# ESC.net
KiCad netlist of a schematic drawn in Altium Designer
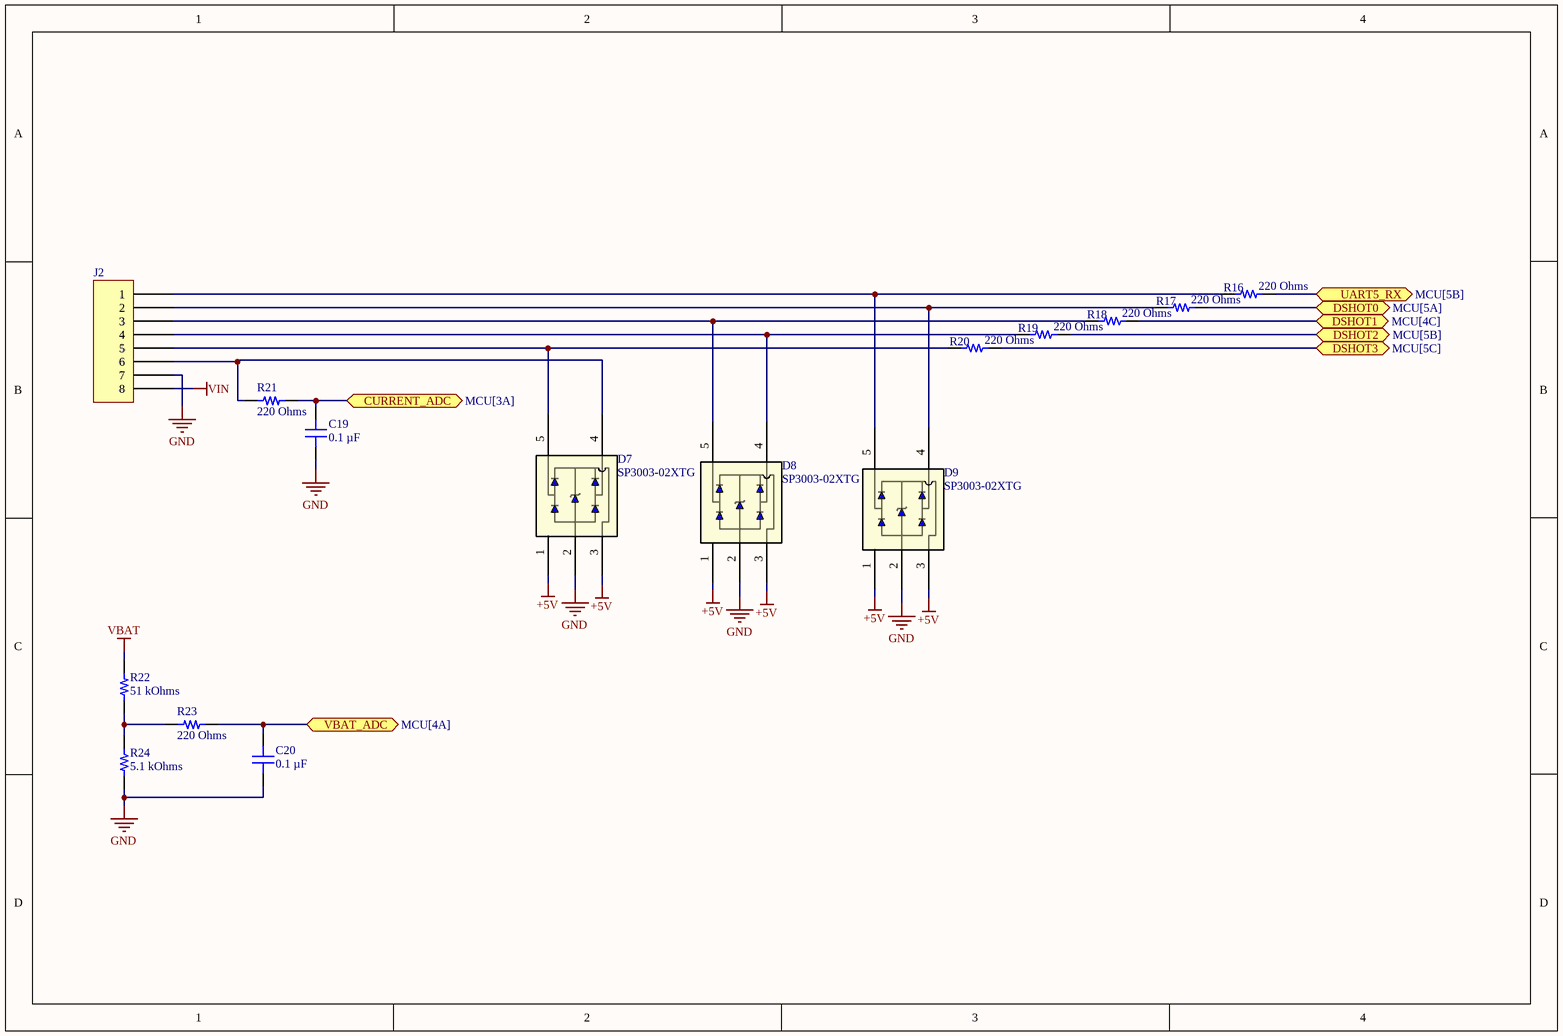
[diagram p0: ESC.SchDoc]

(export (version "E")
  (design (tool "Eeschema 10.0.6"))
  (components
    (comp (ref "C19")
      (value "0.1 µF")
      (footprint "CAP 0402_1005")
      (description "CAP CER 0.1UF 25V X7R 0402")
      (fields
        (field (name "PART NUMBER") "CGA2B3X7R1E104K050BB")
        (field (name "CAPACITANCE") "0.1 µF")
        (field (name "MANUFACTURER") "TDK Corporation")
      )
      (libsource (lib "Celestial Altium Library - altium_library") (part "Capacitor"))
    )
    (comp (ref "C20")
      (value "0.1 µF")
      (footprint "CAP 0402_1005")
      (description "CAP CER 0.1UF 25V X7R 0402")
      (fields
        (field (name "PART NUMBER") "CGA2B3X7R1E104K050BB")
        (field (name "CAPACITANCE") "0.1 µF")
        (field (name "MANUFACTURER") "TDK Corporation")
      )
      (libsource (lib "Celestial Altium Library - altium_library") (part "Capacitor"))
    )
    (comp (ref "D7")
      (value "SP3003-02XTG")
      (footprint "SP3003-02XTG")
      (description "15V Clamp 2.5A (8/20µs) Ipp Tvs Diode Surface Mount SOT-553")
      (fields (field (name "MANUFACTURER") "Littelfuse Inc."))
      (libsource (lib "PCB_Lib") (part "SP3003-02XTG"))
    )
    (comp (ref "D8")
      (value "SP3003-02XTG")
      (footprint "SP3003-02XTG")
      (description "15V Clamp 2.5A (8/20µs) Ipp Tvs Diode Surface Mount SOT-553")
      (fields (field (name "MANUFACTURER") "Littelfuse Inc."))
      (libsource (lib "PCB_Lib") (part "SP3003-02XTG"))
    )
    (comp (ref "D9")
      (value "SP3003-02XTG")
      (footprint "SP3003-02XTG")
      (description "15V Clamp 2.5A (8/20µs) Ipp Tvs Diode Surface Mount SOT-553")
      (fields (field (name "MANUFACTURER") "Littelfuse Inc."))
      (libsource (lib "PCB_Lib") (part "SP3003-02XTG"))
    )
    (comp (ref "J2")
      (value "SM08B-SRSS-TB(LF)(SN)")
      (footprint "JST SM08B-SRSS-TB")
      (description "CONN HEADER SMD R/A 8POS 1MM")
      (fields (field (name "MANUFACTURER") "JST Sales America Inc."))
      (libsource (lib "Celestial Altium Library - altium_library") (part "8 Pin"))
    )
    (comp (ref "R16")
      (value "220 Ohms")
      (footprint "YAGEO RES 0402_1005")
      (description "RES SMD 220 OHM 5% 1/16W 0402")
      (fields (field (name "PART NUMBER") "AC0402JR-07220RL") (field (name "MANUFACTURER") "Yageo"))
      (libsource (lib "Celestial Altium Library - altium_library") (part "Resistor"))
    )
    (comp (ref "R17")
      (value "220 Ohms")
      (footprint "YAGEO RES 0402_1005")
      (description "RES SMD 220 OHM 5% 1/16W 0402")
      (fields (field (name "PART NUMBER") "AC0402JR-07220RL") (field (name "MANUFACTURER") "Yageo"))
      (libsource (lib "Celestial Altium Library - altium_library") (part "Resistor"))
    )
    (comp (ref "R18")
      (value "220 Ohms")
      (footprint "YAGEO RES 0402_1005")
      (description "RES SMD 220 OHM 5% 1/16W 0402")
      (fields (field (name "PART NUMBER") "AC0402JR-07220RL") (field (name "MANUFACTURER") "Yageo"))
      (libsource (lib "Celestial Altium Library - altium_library") (part "Resistor"))
    )
    (comp (ref "R19")
      (value "220 Ohms")
      (footprint "YAGEO RES 0402_1005")
      (description "RES SMD 220 OHM 5% 1/16W 0402")
      (fields (field (name "PART NUMBER") "AC0402JR-07220RL") (field (name "MANUFACTURER") "Yageo"))
      (libsource (lib "Celestial Altium Library - altium_library") (part "Resistor"))
    )
    (comp (ref "R20")
      (value "220 Ohms")
      (footprint "YAGEO RES 0402_1005")
      (description "RES SMD 220 OHM 5% 1/16W 0402")
      (fields (field (name "PART NUMBER") "AC0402JR-07220RL") (field (name "MANUFACTURER") "Yageo"))
      (libsource (lib "Celestial Altium Library - altium_library") (part "Resistor"))
    )
    (comp (ref "R21")
      (value "220 Ohms")
      (footprint "YAGEO RES 0402_1005")
      (description "RES SMD 220 OHM 5% 1/16W 0402")
      (fields (field (name "PART NUMBER") "AC0402JR-07220RL") (field (name "MANUFACTURER") "Yageo"))
      (libsource (lib "Celestial Altium Library - altium_library") (part "Resistor"))
    )
    (comp (ref "R22")
      (value "51 kOhms")
      (footprint "RES 0603_1608")
      (description "RES SMD 51K OHM 1% 1/3W 0603")
      (fields (field (name "PART NUMBER") "CRCW060351K0FKEAHP") (field (name "MANUFACTURER") "Vishay Dale"))
      (libsource (lib "Celestial Altium Library - altium_library") (part "Resistor"))
    )
    (comp (ref "R23")
      (value "220 Ohms")
      (footprint "YAGEO RES 0402_1005")
      (description "RES SMD 220 OHM 5% 1/16W 0402")
      (fields (field (name "PART NUMBER") "AC0402JR-07220RL") (field (name "MANUFACTURER") "Yageo"))
      (libsource (lib "Celestial Altium Library - altium_library") (part "Resistor"))
    )
    (comp (ref "R24")
      (value "5.1 kOhms")
      (footprint "RES 0603_1608")
      (description "RES SMD 5.1K OHM 1% 1/3W 0603")
      (fields
        (field (name "PART NUMBER") "ERJ-PA3F5101V")
        (field (name "MANUFACTURER") "Panasonic Electronic Components")
      )
      (libsource (lib "Celestial Altium Library - altium_library") (part "Resistor"))
    )
  )
  (nets
    (net (code "1") (name "+5V") (class "Default")
      (node (ref "D7") (pin "1") (pinfunction "1_1") (pintype "passive"))
      (node (ref "D7") (pin "3") (pinfunction "3_3") (pintype "passive"))
      (node (ref "D8") (pin "1") (pinfunction "1_1") (pintype "passive"))
      (node (ref "D8") (pin "3") (pinfunction "3_3") (pintype "passive"))
      (node (ref "D9") (pin "1") (pinfunction "1_1") (pintype "passive"))
      (node (ref "D9") (pin "3") (pinfunction "3_3") (pintype "passive"))
    )
    (net (code "2") (name "/CURRENT_ADC") (class "Default")
      (node (ref "C19") (pin "1") (pinfunction "1_1") (pintype "passive"))
      (node (ref "R21") (pin "1") (pinfunction "1_1") (pintype "passive"))
    )
    (net (code "3") (name "/DSHOT0") (class "Default")
      (node (ref "R17") (pin "2") (pinfunction "2_2") (pintype "passive"))
    )
    (net (code "4") (name "/DSHOT1") (class "Default")
      (node (ref "R18") (pin "2") (pinfunction "2_2") (pintype "passive"))
    )
    (net (code "5") (name "/DSHOT2") (class "Default")
      (node (ref "R19") (pin "2") (pinfunction "2_2") (pintype "passive"))
    )
    (net (code "6") (name "/DSHOT3") (class "Default")
      (node (ref "R20") (pin "2") (pinfunction "2_2") (pintype "passive"))
    )
    (net (code "7") (name "/UART5_RX") (class "Default")
      (node (ref "R16") (pin "2") (pinfunction "2_2") (pintype "passive"))
    )
    (net (code "8") (name "/VBAT_ADC") (class "Default")
      (node (ref "C20") (pin "2") (pinfunction "2_2") (pintype "passive"))
      (node (ref "R23") (pin "2") (pinfunction "2_2") (pintype "passive"))
    )
    (net (code "9") (name "GND") (class "Default")
      (node (ref "C19") (pin "2") (pinfunction "2_2") (pintype "passive"))
      (node (ref "C20") (pin "1") (pinfunction "1_1") (pintype "passive"))
      (node (ref "D7") (pin "2") (pinfunction "2_2") (pintype "passive"))
      (node (ref "D8") (pin "2") (pinfunction "2_2") (pintype "passive"))
      (node (ref "D9") (pin "2") (pinfunction "2_2") (pintype "passive"))
      (node (ref "J2") (pin "7") (pinfunction "7_7") (pintype "passive"))
      (node (ref "R24") (pin "1") (pinfunction "1_1") (pintype "passive"))
    )
    (net (code "10") (name "Net-(D7-Pad4)") (class "Default")
      (node (ref "D7") (pin "4") (pinfunction "4_4") (pintype "passive"))
      (node (ref "J2") (pin "6") (pinfunction "6_6") (pintype "passive"))
      (node (ref "R21") (pin "2") (pinfunction "2_2") (pintype "passive"))
    )
    (net (code "11") (name "Net-(D7-Pad5)") (class "Default")
      (node (ref "D7") (pin "5") (pinfunction "5_5") (pintype "passive"))
      (node (ref "J2") (pin "5") (pinfunction "5_5") (pintype "passive"))
      (node (ref "R20") (pin "1") (pinfunction "1_1") (pintype "passive"))
    )
    (net (code "12") (name "Net-(D8-Pad4)") (class "Default")
      (node (ref "D8") (pin "4") (pinfunction "4_4") (pintype "passive"))
      (node (ref "J2") (pin "4") (pinfunction "4_4") (pintype "passive"))
      (node (ref "R19") (pin "1") (pinfunction "1_1") (pintype "passive"))
    )
    (net (code "13") (name "Net-(D8-Pad5)") (class "Default")
      (node (ref "D8") (pin "5") (pinfunction "5_5") (pintype "passive"))
      (node (ref "J2") (pin "3") (pinfunction "3_3") (pintype "passive"))
      (node (ref "R18") (pin "1") (pinfunction "1_1") (pintype "passive"))
    )
    (net (code "14") (name "Net-(D9-Pad4)") (class "Default")
      (node (ref "D9") (pin "4") (pinfunction "4_4") (pintype "passive"))
      (node (ref "J2") (pin "2") (pinfunction "2_2") (pintype "passive"))
      (node (ref "R17") (pin "1") (pinfunction "1_1") (pintype "passive"))
    )
    (net (code "15") (name "Net-(D9-Pad5)") (class "Default")
      (node (ref "D9") (pin "5") (pinfunction "5_5") (pintype "passive"))
      (node (ref "J2") (pin "1") (pinfunction "1_1") (pintype "passive"))
      (node (ref "R16") (pin "1") (pinfunction "1_1") (pintype "passive"))
    )
    (net (code "16") (name "Net-(R22-Pad1)") (class "Default")
      (node (ref "R22") (pin "1") (pinfunction "1_1") (pintype "passive"))
      (node (ref "R23") (pin "1") (pinfunction "1_1") (pintype "passive"))
      (node (ref "R24") (pin "2") (pinfunction "2_2") (pintype "passive"))
    )
    (net (code "17") (name "VBAT") (class "Default")
      (node (ref "R22") (pin "2") (pinfunction "2_2") (pintype "passive"))
    )
    (net (code "18") (name "VIN") (class "Default")
      (node (ref "J2") (pin "8") (pinfunction "8_8") (pintype "passive"))
    )
  )
)
